# NanoV3_3.net
KiCad netlist of a schematic drawn in EAGLE
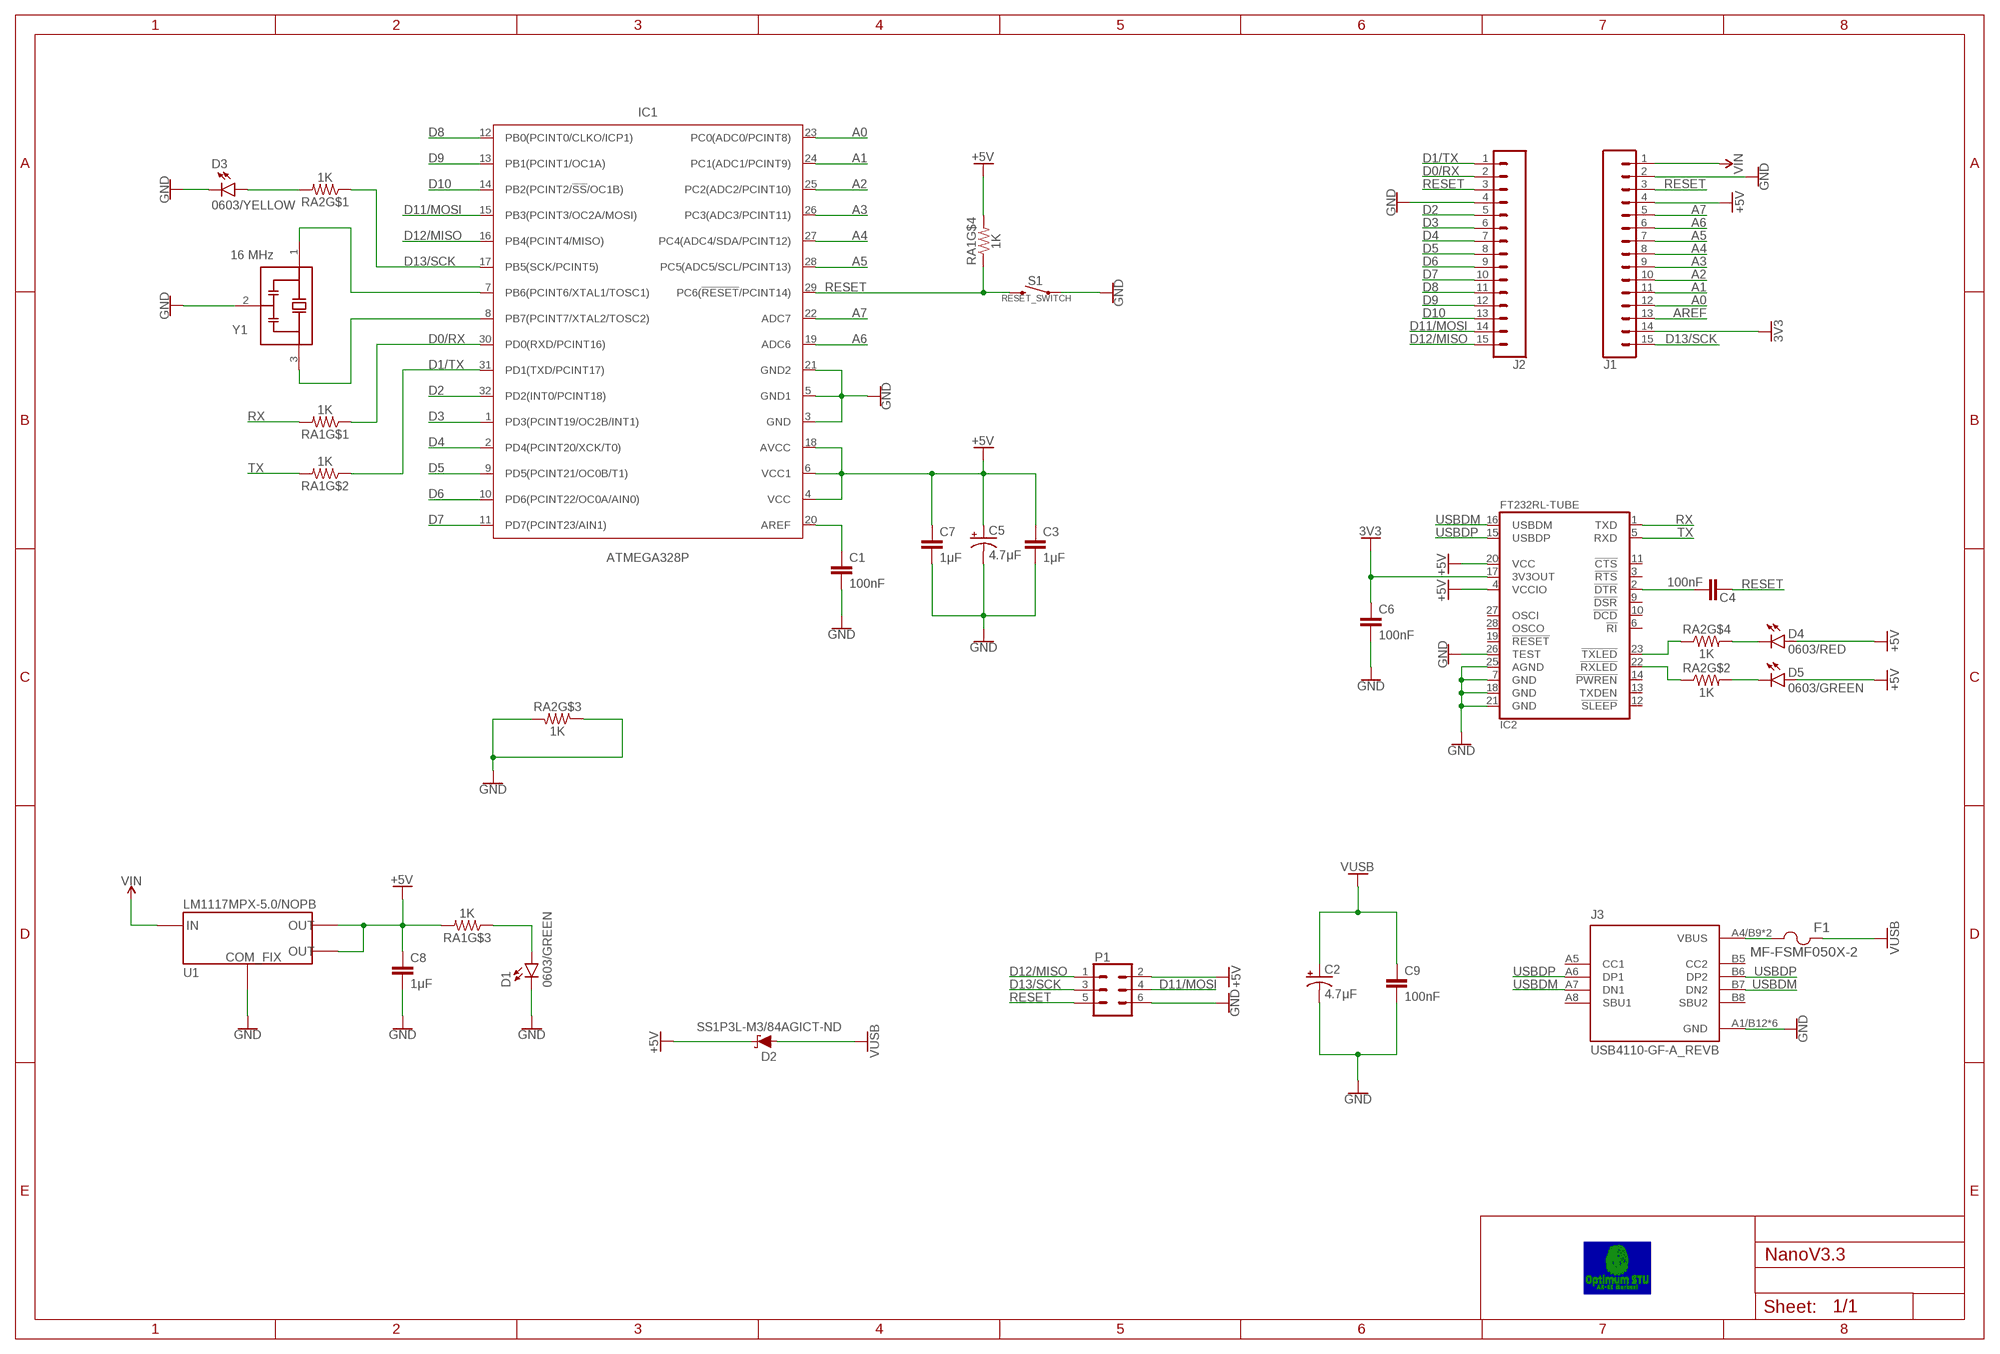
[diagram p0: schematic, sheet 1]

(export (version "E")
  (design (tool "Eeschema 10.0.6"))
  (components
    (comp (ref "C1")
      (value "100nF")
      (footprint "eagle-import:CAP_0603(1608_METRIC)")
      (libsource (lib "eagle-import") (part "100NF_0603(1608METRIC)_±10%_16V_CERAMIC_CAPACITOR_X7R"))
    )
    (comp (ref "C2")
      (value "4.7μF")
      (footprint "eagle-import:CAP_TANT_1206(3216_METRIC)_TYPE_A_MAX")
      (libsource (lib "eagle-import") (part "4.7UF_TANTALUM_CAPACITOR_MOLDED_1206(3216_METRIC)_TYPE_A_16V_4OHM"))
    )
    (comp (ref "C3")
      (value "1μF")
      (footprint "eagle-import:CAP_0603(1608_METRIC)")
      (libsource (lib "eagle-import") (part "1UF_0603(1608METRIC)_±10%_16V_CERAMIC_CAPACITOR_X7R"))
    )
    (comp (ref "C4")
      (value "100nF")
      (footprint "eagle-import:CAP_0603(1608_METRIC)")
      (libsource (lib "eagle-import") (part "100NF_0603(1608METRIC)_±10%_16V_CERAMIC_CAPACITOR_X7R"))
    )
    (comp (ref "C5")
      (value "4.7μF")
      (footprint "eagle-import:CAP_TANT_1206(3216_METRIC)_TYPE_A_MAX")
      (libsource (lib "eagle-import") (part "4.7UF_TANTALUM_CAPACITOR_MOLDED_1206(3216_METRIC)_TYPE_A_16V_4OHM"))
    )
    (comp (ref "C6")
      (value "100nF")
      (footprint "eagle-import:CAP_0603(1608_METRIC)")
      (libsource (lib "eagle-import") (part "100NF_0603(1608METRIC)_±10%_16V_CERAMIC_CAPACITOR_X7R"))
    )
    (comp (ref "C7")
      (value "1μF")
      (footprint "eagle-import:CAP_0603(1608_METRIC)")
      (libsource (lib "eagle-import") (part "1UF_0603(1608METRIC)_±10%_16V_CERAMIC_CAPACITOR_X7R"))
    )
    (comp (ref "C8")
      (value "1μF")
      (footprint "eagle-import:CAP_0603(1608_METRIC)")
      (libsource (lib "eagle-import") (part "1UF_0603(1608METRIC)_±10%_16V_CERAMIC_CAPACITOR_X7R"))
    )
    (comp (ref "C9")
      (value "100nF")
      (footprint "eagle-import:CAP_0603(1608_METRIC)")
      (libsource (lib "eagle-import") (part "100NF_0603(1608METRIC)_±10%_16V_CERAMIC_CAPACITOR_X7R"))
    )
    (comp (ref "D1")
      (value "0603/GREEN")
      (footprint "eagle-import:LED_0603(1608_METRIC)_GREEN")
      (libsource (lib "eagle-import") (part "LED_GREEN_571NM_0603(1608_METRIC)_INDICATION-DISCRETE_2V"))
    )
    (comp (ref "D2")
      (value "SS1P3L-M3/84AGICT-ND")
      (footprint "eagle-import:DO-220AA(SMP)-M")
      (fields
        (field (name "MANUFACTURER_PART_NUMBER") "SS1P3L-M3/84A")
        (field (name "COPYRIGHT") "Copyright (C) 2022 Ultra Librarian. All rights reserved.")
      )
      (libsource (lib "eagle-import") (part "SS1P3L-M3/84ADIODE_SS1P3L-M3/84A_VIS-M"))
    )
    (comp (ref "D3")
      (value "0603/YELLOW")
      (footprint "eagle-import:LED_0603(1608_METRIC)_YELLOW")
      (libsource (lib "eagle-import") (part "LED_YELLOW_591NM_0603(1608_METRIC)_INDICATION-DISCRETE_2.1V"))
    )
    (comp (ref "D4")
      (value "0603/RED")
      (footprint "eagle-import:LED_0603(1608_METRIC)_RED")
      (libsource (lib "eagle-import") (part "LED_RED_631NM_0603(1608_METRIC)_INDICATION-DISCRETE_2V"))
    )
    (comp (ref "D5")
      (value "0603/GREEN")
      (footprint "eagle-import:LED_0603(1608_METRIC)_GREEN")
      (libsource (lib "eagle-import") (part "LED_GREEN_571NM_0603(1608_METRIC)_INDICATION-DISCRETE_2V"))
    )
    (comp (ref "F1")
      (value "MF-FSMF050X-2")
      (footprint "eagle-import:PTC_FUSE_0603(1608_METRIC)")
      (fields (field (name "COPYRIGHT") "Copyright (C) 2022 Ultra Librarian. All rights reserved."))
      (libsource (lib "eagle-import") (part "MF-FSMF050X-2"))
    )
    (comp (ref "IC1")
      (value "ATMEGA328P")
      (footprint "eagle-import:32-TQFP")
      (fields (field (name "MANUFACTURER") "Microchip") (field (name "MPN") "ATmega328P-MMH"))
      (libsource (lib "eagle-import") (part "ATMEGA328P_TQFP"))
    )
    (comp (ref "IC2")
      (value "FT232RL-TUBE")
      (footprint "eagle-import:28-SSOP")
      (fields (field (name "DIGI-KEY_PART_NUMBER") "768-1306-ND") (field (name "MF") "FTDI,"))
      (libsource (lib "eagle-import") (part "FT232RL-TUBE"))
    )
    (comp (ref "J1")
      (value "CONN_15_M_180C")
      (footprint "eagle-import:HDRV15W64P254_1X15_3810X254X838B")
      (libsource (lib "eagle-import") (part "CONN_15_M_180C"))
    )
    (comp (ref "J2")
      (value "CONN_15_M_180C")
      (footprint "eagle-import:HDRV15W64P254_1X15_3810X254X838B")
      (libsource (lib "eagle-import") (part "CONN_15_M_180C"))
    )
    (comp (ref "J3")
      (value "USB4110-GF-A_REVB")
      (footprint "eagle-import:GCT_USB4110-GF-A_REVB")
      (fields (field (name "MF") "GCT") (field (name "MP") "USB4110-GF-A"))
      (libsource (lib "eagle-import") (part "USB4110-GF-A_REVB"))
    )
    (comp (ref "P1")
      (value "CONN_2X3_M_180C")
      (footprint "eagle-import:HDRV6W64P254_2X3_762X508X838B")
      (libsource (lib "eagle-import") (part "CONN_2X3_M_180C"))
    )
    (comp (ref "RA1")
      (value "1K")
      (footprint "eagle-import:RESISTOR_ARRAY_1206(3216_METRIC)_WIDE")
      (libsource (lib "eagle-import") (part "1KOHM_ARRAY_4_ELEMENT_ISOLATED_NETWORK/ARRAY_±5%_62.5MW_FOR_PER_RESISTOR_±200PPM/°C_1206(3216_METRIC),CONVEX,LONG_SIDE_TERMINALS"))
    )
    (comp (ref "RA2")
      (value "1K")
      (footprint "eagle-import:RESISTOR_ARRAY_1206(3216_METRIC)_WIDE")
      (libsource (lib "eagle-import") (part "1KOHM_ARRAY_4_ELEMENT_ISOLATED_NETWORK/ARRAY_±5%_62.5MW_FOR_PER_RESISTOR_±200PPM/°C_1206(3216_METRIC),CONVEX,LONG_SIDE_TERMINALS"))
    )
    (comp (ref "S1")
      (value "RESET SWITCH")
      (footprint "eagle-import:SW_TS09-63-25-WT-260-SMT-TR")
      (libsource (lib "eagle-import") (part "RS-282C05A3-SM_RT"))
    )
    (comp (ref "U1")
      (value "LM1117MPX-5.0/NOPB")
      (footprint "eagle-import:SOT-223-4")
      (libsource (lib "eagle-import") (part "LM1117MPX-5.0/NOPB_LINEAR_VOLTAGE_REGULATOR_IC_POSITIVE_FIXED_1OUTPUT_800MA_SOT-223-4"))
    )
    (comp (ref "Y1")
      (value "16 MHz")
      (footprint "eagle-import:RESONATOR_SMD-3(3.20MMX1.30MM)")
      (fields
        (field (name "DIGI-KEY_PART_NUMBER") "490-CSTNE16M0V53L000R0TR-ND")
        (field (name "MF") "Murata Electronics")
        (field (name "MP") "CSTNE16M0V53L000R0")
      )
      (libsource (lib "eagle-import") (part "CSTNE16M0V53L000R0_16MHZ_CERAMIC_RESONATOR_BUILT-IN_CAPACITOR_15PF_±0.2%_40OHMS-40°C~85°C_SURFACE_MOUNT"))
    )
  )
  (nets
    (net (code "1") (name "+5V") (class "Default")
      (node (ref "C3") (pin "1") (pinfunction "1_1") (pintype "passive"))
      (node (ref "C5") (pin "1") (pinfunction "+_1") (pintype "passive"))
      (node (ref "C7") (pin "1") (pinfunction "1_1") (pintype "passive"))
      (node (ref "C8") (pin "1") (pinfunction "1_1") (pintype "passive"))
      (node (ref "D2") (pin "1") (pinfunction "C_1") (pintype "passive"))
      (node (ref "D4") (pin "A") (pinfunction "A_A") (pintype "passive"))
      (node (ref "D5") (pin "A") (pinfunction "A_A") (pintype "passive"))
      (node (ref "IC1") (pin "18") (pinfunction "AVCC_18") (pintype "power_in"))
      (node (ref "IC1") (pin "4") (pinfunction "VCC_4") (pintype "power_in"))
      (node (ref "IC1") (pin "6") (pinfunction "VCC1_6") (pintype "power_in"))
      (node (ref "IC2") (pin "20") (pinfunction "VCC_20") (pintype "power_in"))
      (node (ref "IC2") (pin "4") (pinfunction "VCCIO_4") (pintype "power_in"))
      (node (ref "J1") (pin "4") (pinfunction "4_4") (pintype "passive"))
      (node (ref "P1") (pin "2") (pinfunction "2_2") (pintype "bidirectional"))
      (node (ref "RA1") (pin "5") (pinfunction "2_5") (pintype "passive"))
      (node (ref "RA1") (pin "6") (pinfunction "2_6") (pintype "passive"))
      (node (ref "U1") (pin "2") (pinfunction "OUTPUT_JUNCTİON_2") (pintype "output"))
      (node (ref "U1") (pin "4") (pinfunction "OUTPUT_TAB_4") (pintype "output"))
    )
    (net (code "2") (name "/A0") (class "Default")
      (node (ref "IC1") (pin "23") (pinfunction "PC0(ADC0/PCINT8)_23") (pintype "bidirectional"))
      (node (ref "J1") (pin "12") (pinfunction "12_12") (pintype "passive"))
    )
    (net (code "3") (name "/A1") (class "Default")
      (node (ref "IC1") (pin "24") (pinfunction "PC1(ADC1/PCINT9)_24") (pintype "bidirectional"))
      (node (ref "J1") (pin "11") (pinfunction "11_11") (pintype "passive"))
    )
    (net (code "4") (name "/A2") (class "Default")
      (node (ref "IC1") (pin "25") (pinfunction "PC2(ADC2/PCINT10)_25") (pintype "bidirectional"))
      (node (ref "J1") (pin "10") (pinfunction "10_10") (pintype "passive"))
    )
    (net (code "5") (name "/A3") (class "Default")
      (node (ref "IC1") (pin "26") (pinfunction "PC3(ADC3/PCINT11)_26") (pintype "bidirectional"))
      (node (ref "J1") (pin "9") (pinfunction "9_9") (pintype "passive"))
    )
    (net (code "6") (name "/A4") (class "Default")
      (node (ref "IC1") (pin "27") (pinfunction "PC4(ADC4/SDA/PCINT12)_27") (pintype "bidirectional"))
      (node (ref "J1") (pin "8") (pinfunction "8_8") (pintype "passive"))
    )
    (net (code "7") (name "/A5") (class "Default")
      (node (ref "IC1") (pin "28") (pinfunction "PC5(ADC5/SCL/PCINT13)_28") (pintype "bidirectional"))
      (node (ref "J1") (pin "7") (pinfunction "7_7") (pintype "passive"))
    )
    (net (code "8") (name "/A6") (class "Default")
      (node (ref "IC1") (pin "19") (pinfunction "ADC6_19") (pintype "bidirectional"))
      (node (ref "J1") (pin "6") (pinfunction "6_6") (pintype "passive"))
    )
    (net (code "9") (name "/A7") (class "Default")
      (node (ref "IC1") (pin "22") (pinfunction "ADC7_22") (pintype "bidirectional"))
      (node (ref "J1") (pin "5") (pinfunction "5_5") (pintype "passive"))
    )
    (net (code "10") (name "/AREF") (class "Default")
      (node (ref "C1") (pin "1") (pinfunction "1_1") (pintype "passive"))
      (node (ref "IC1") (pin "20") (pinfunction "AREF_20") (pintype "power_in"))
      (node (ref "J1") (pin "13") (pinfunction "13_13") (pintype "passive"))
    )
    (net (code "11") (name "/D0{slash}RX") (class "Default")
      (node (ref "IC1") (pin "30") (pinfunction "PD0(RXD/PCINT16)_30") (pintype "bidirectional"))
      (node (ref "J2") (pin "2") (pinfunction "2_2") (pintype "passive"))
      (node (ref "RA1") (pin "1") (pinfunction "1_1") (pintype "passive"))
    )
    (net (code "12") (name "/D1{slash}TX") (class "Default")
      (node (ref "IC1") (pin "31") (pinfunction "PD1(TXD/PCINT17)_31") (pintype "bidirectional"))
      (node (ref "J2") (pin "1") (pinfunction "1_1") (pintype "passive"))
      (node (ref "RA1") (pin "2") (pinfunction "1_2") (pintype "passive"))
    )
    (net (code "13") (name "/D2") (class "Default")
      (node (ref "IC1") (pin "32") (pinfunction "PD2(INT0/PCINT18)_32") (pintype "bidirectional"))
      (node (ref "J2") (pin "5") (pinfunction "5_5") (pintype "passive"))
    )
    (net (code "14") (name "/D3") (class "Default")
      (node (ref "IC1") (pin "1") (pinfunction "PD3(PCINT19/OC2B/INT1)_1") (pintype "bidirectional"))
      (node (ref "J2") (pin "6") (pinfunction "6_6") (pintype "passive"))
    )
    (net (code "15") (name "/D4") (class "Default")
      (node (ref "IC1") (pin "2") (pinfunction "PD4(PCINT20/XCK/T0)_2") (pintype "bidirectional"))
      (node (ref "J2") (pin "7") (pinfunction "7_7") (pintype "passive"))
    )
    (net (code "16") (name "/D5") (class "Default")
      (node (ref "IC1") (pin "9") (pinfunction "PD5(PCINT21/OC0B/T1)_9") (pintype "bidirectional"))
      (node (ref "J2") (pin "8") (pinfunction "8_8") (pintype "passive"))
    )
    (net (code "17") (name "/D6") (class "Default")
      (node (ref "IC1") (pin "10") (pinfunction "PD6(PCINT22/OC0A/AIN0)_10") (pintype "bidirectional"))
      (node (ref "J2") (pin "9") (pinfunction "9_9") (pintype "passive"))
    )
    (net (code "18") (name "/D7") (class "Default")
      (node (ref "IC1") (pin "11") (pinfunction "PD7(PCINT23/AIN1)_11") (pintype "bidirectional"))
      (node (ref "J2") (pin "10") (pinfunction "10_10") (pintype "passive"))
    )
    (net (code "19") (name "/D8") (class "Default")
      (node (ref "IC1") (pin "12") (pinfunction "PB0(PCINT0/CLKO/ICP1)_12") (pintype "bidirectional"))
      (node (ref "J2") (pin "11") (pinfunction "11_11") (pintype "passive"))
    )
    (net (code "20") (name "/D9") (class "Default")
      (node (ref "IC1") (pin "13") (pinfunction "PB1(PCINT1/OC1A)_13") (pintype "bidirectional"))
      (node (ref "J2") (pin "12") (pinfunction "12_12") (pintype "passive"))
    )
    (net (code "21") (name "/D10") (class "Default")
      (node (ref "IC1") (pin "14") (pinfunction "PB2(PCINT2/~{SS}/OC1B)_14") (pintype "bidirectional"))
      (node (ref "J2") (pin "13") (pinfunction "13_13") (pintype "passive"))
    )
    (net (code "22") (name "/D11{slash}MOSI") (class "Default")
      (node (ref "IC1") (pin "15") (pinfunction "PB3(PCINT3/OC2A/MOSI)_15") (pintype "bidirectional"))
      (node (ref "J2") (pin "14") (pinfunction "14_14") (pintype "passive"))
      (node (ref "P1") (pin "4") (pinfunction "4_4") (pintype "bidirectional"))
    )
    (net (code "23") (name "/D12{slash}MISO") (class "Default")
      (node (ref "IC1") (pin "16") (pinfunction "PB4(PCINT4/MISO)_16") (pintype "bidirectional"))
      (node (ref "J2") (pin "15") (pinfunction "15_15") (pintype "passive"))
      (node (ref "P1") (pin "1") (pinfunction "1_1") (pintype "bidirectional"))
    )
    (net (code "24") (name "/D13{slash}SCK") (class "Default")
      (node (ref "IC1") (pin "17") (pinfunction "PB5(SCK/PCINT5)_17") (pintype "bidirectional"))
      (node (ref "J1") (pin "15") (pinfunction "15_15") (pintype "passive"))
      (node (ref "P1") (pin "3") (pinfunction "3_3") (pintype "bidirectional"))
      (node (ref "RA2") (pin "1") (pinfunction "1_1") (pintype "passive"))
    )
    (net (code "25") (name "/RESET") (class "Default")
      (node (ref "C4") (pin "1") (pinfunction "1_1") (pintype "passive"))
      (node (ref "IC1") (pin "29") (pinfunction "PC6(~{RESET}/PCINT14)_29") (pintype "bidirectional"))
      (node (ref "J1") (pin "3") (pinfunction "3_3") (pintype "passive"))
      (node (ref "J2") (pin "3") (pinfunction "3_3") (pintype "passive"))
      (node (ref "P1") (pin "5") (pinfunction "5_5") (pintype "bidirectional"))
      (node (ref "RA1") (pin "4") (pinfunction "1_4") (pintype "passive"))
      (node (ref "S1") (pin "2") (pinfunction "2_2") (pintype "passive"))
    )
    (net (code "26") (name "/RX") (class "Default")
      (node (ref "IC2") (pin "1") (pinfunction "TXD_1") (pintype "output"))
      (node (ref "RA1") (pin "8") (pinfunction "2_8") (pintype "passive"))
    )
    (net (code "27") (name "/TX") (class "Default")
      (node (ref "IC2") (pin "5") (pinfunction "RXD_5") (pintype "input"))
      (node (ref "RA1") (pin "7") (pinfunction "2_7") (pintype "passive"))
    )
    (net (code "28") (name "/USBDM") (class "Default")
      (node (ref "IC2") (pin "16") (pinfunction "USBDM_16") (pintype "bidirectional"))
      (node (ref "J3") (pin "A7") (pinfunction "DN1_A7") (pintype "bidirectional"))
      (node (ref "J3") (pin "B7") (pinfunction "DN2_B7") (pintype "bidirectional"))
    )
    (net (code "29") (name "/USBDP") (class "Default")
      (node (ref "IC2") (pin "15") (pinfunction "USBDP_15") (pintype "bidirectional"))
      (node (ref "J3") (pin "A6") (pinfunction "DP1_A6") (pintype "bidirectional"))
      (node (ref "J3") (pin "B6") (pinfunction "DP2_B6") (pintype "bidirectional"))
    )
    (net (code "30") (name "3V3") (class "Default")
      (node (ref "C6") (pin "1") (pinfunction "1_1") (pintype "passive"))
      (node (ref "IC2") (pin "17") (pinfunction "3V3OUT_17") (pintype "power_in"))
      (node (ref "J1") (pin "14") (pinfunction "14_14") (pintype "passive"))
    )
    (net (code "31") (name "GND") (class "Default")
      (node (ref "C1") (pin "2") (pinfunction "2_2") (pintype "passive"))
      (node (ref "C2") (pin "2") (pinfunction "-_2") (pintype "passive"))
      (node (ref "C3") (pin "2") (pinfunction "2_2") (pintype "passive"))
      (node (ref "C5") (pin "2") (pinfunction "-_2") (pintype "passive"))
      (node (ref "C6") (pin "2") (pinfunction "2_2") (pintype "passive"))
      (node (ref "C7") (pin "2") (pinfunction "2_2") (pintype "passive"))
      (node (ref "C8") (pin "2") (pinfunction "2_2") (pintype "passive"))
      (node (ref "C9") (pin "2") (pinfunction "2_2") (pintype "passive"))
      (node (ref "D1") (pin "C") (pinfunction "C_C") (pintype "passive"))
      (node (ref "D3") (pin "C") (pinfunction "C_C") (pintype "passive"))
      (node (ref "IC1") (pin "21") (pinfunction "GND2_21") (pintype "passive"))
      (node (ref "IC1") (pin "3") (pinfunction "GND_3") (pintype "passive"))
      (node (ref "IC1") (pin "5") (pinfunction "GND1_5") (pintype "passive"))
      (node (ref "IC2") (pin "18") (pinfunction "GND_18") (pintype "power_in"))
      (node (ref "IC2") (pin "21") (pinfunction "GND_21") (pintype "power_in"))
      (node (ref "IC2") (pin "25") (pinfunction "AGND_25") (pintype "power_in"))
      (node (ref "IC2") (pin "26") (pinfunction "TEST_26") (pintype "input"))
      (node (ref "IC2") (pin "7") (pinfunction "GND_7") (pintype "power_in"))
      (node (ref "J1") (pin "2") (pinfunction "2_2") (pintype "passive"))
      (node (ref "J2") (pin "4") (pinfunction "4_4") (pintype "passive"))
      (node (ref "J3") (pin "A1/B12") (pinfunction "GND_A1/B12") (pintype "power_in"))
      (node (ref "J3") (pin "B1/A12") (pinfunction "GND_B1/A12") (pintype "power_in"))
      (node (ref "J3") (pin "S1") (pinfunction "GND_S1") (pintype "power_in"))
      (node (ref "J3") (pin "S2") (pinfunction "GND_S2") (pintype "power_in"))
      (node (ref "J3") (pin "S3") (pinfunction "GND_S3") (pintype "power_in"))
      (node (ref "J3") (pin "S4") (pinfunction "GND_S4") (pintype "power_in"))
      (node (ref "P1") (pin "6") (pinfunction "6_6") (pintype "bidirectional"))
      (node (ref "RA2") (pin "3") (pinfunction "1_3") (pintype "passive"))
      (node (ref "RA2") (pin "6") (pinfunction "2_6") (pintype "passive"))
      (node (ref "S1") (pin "1") (pinfunction "1_1") (pintype "passive"))
      (node (ref "U1") (pin "1") (pinfunction "COMMON_FIXED_1") (pintype "input"))
      (node (ref "Y1") (pin "2") (pinfunction "GND_2") (pintype "power_in"))
    )
    (net (code "32") (name "Net-(F1-Pad1)") (class "Default")
      (node (ref "F1") (pin "1") (pinfunction "1_1") (pintype "passive"))
      (node (ref "J3") (pin "A4/B9") (pinfunction "VBUS_A4/B9") (pintype "power_in"))
      (node (ref "J3") (pin "B4/A9") (pinfunction "VBUS_B4/A9") (pintype "power_in"))
    )
    (net (code "33") (name "Net-(IC1-PB6(PCINT6{slash}XTAL1{slash}TOSC1))") (class "Default")
      (node (ref "IC1") (pin "7") (pinfunction "PB6(PCINT6/XTAL1/TOSC1)_7") (pintype "input"))
      (node (ref "Y1") (pin "1") (pinfunction "IN_1") (pintype "input"))
    )
    (net (code "34") (name "Net-(IC1-PB7(PCINT7{slash}XTAL2{slash}TOSC2))") (class "Default")
      (node (ref "IC1") (pin "8") (pinfunction "PB7(PCINT7/XTAL2/TOSC2)_8") (pintype "input"))
      (node (ref "Y1") (pin "3") (pinfunction "OUT_3") (pintype "output"))
    )
    (net (code "35") (name "Net-(IC2-~{DTR})") (class "Default")
      (node (ref "C4") (pin "2") (pinfunction "2_2") (pintype "passive"))
      (node (ref "IC2") (pin "2") (pinfunction "~{DTR}_2") (pintype "output"))
    )
    (net (code "36") (name "Net-(IC2-~{RXLED})") (class "Default")
      (node (ref "IC2") (pin "22") (pinfunction "~{RXLED}_22") (pintype "input"))
      (node (ref "RA2") (pin "2") (pinfunction "1_2") (pintype "passive"))
    )
    (net (code "37") (name "Net-(IC2-~{TXLED})") (class "Default")
      (node (ref "IC2") (pin "23") (pinfunction "~{TXLED}_23") (pintype "input"))
      (node (ref "RA2") (pin "4") (pinfunction "1_4") (pintype "passive"))
    )
    (net (code "38") (name "Net-(RA1C-1)") (class "Default")
      (node (ref "D1") (pin "A") (pinfunction "A_A") (pintype "passive"))
      (node (ref "RA1") (pin "3") (pinfunction "1_3") (pintype "passive"))
    )
    (net (code "39") (name "Net-(RA2A-2)") (class "Default")
      (node (ref "D3") (pin "A") (pinfunction "A_A") (pintype "passive"))
      (node (ref "RA2") (pin "8") (pinfunction "2_8") (pintype "passive"))
    )
    (net (code "40") (name "Net-(RA2B-2)") (class "Default")
      (node (ref "D5") (pin "C") (pinfunction "C_C") (pintype "passive"))
      (node (ref "RA2") (pin "7") (pinfunction "2_7") (pintype "passive"))
    )
    (net (code "41") (name "Net-(RA2D-2)") (class "Default")
      (node (ref "D4") (pin "C") (pinfunction "C_C") (pintype "passive"))
      (node (ref "RA2") (pin "5") (pinfunction "2_5") (pintype "passive"))
    )
    (net (code "42") (name "VIN") (class "Default")
      (node (ref "J1") (pin "1") (pinfunction "1_1") (pintype "passive"))
      (node (ref "U1") (pin "3") (pinfunction "INPUT_3") (pintype "input"))
    )
    (net (code "43") (name "VUSB") (class "Default")
      (node (ref "C2") (pin "1") (pinfunction "+_1") (pintype "passive"))
      (node (ref "C9") (pin "1") (pinfunction "1_1") (pintype "passive"))
      (node (ref "D2") (pin "2") (pinfunction "A_2") (pintype "passive"))
      (node (ref "F1") (pin "2") (pinfunction "2_2") (pintype "passive"))
    )
    (net (code "44") (name "unconnected-(IC2-OSCI-Pad27)") (class "Default")
      (node (ref "IC2") (pin "27") (pinfunction "OSCI_27") (pintype "no_connect"))
    )
    (net (code "45") (name "unconnected-(IC2-OSCO-Pad28)") (class "Default")
      (node (ref "IC2") (pin "28") (pinfunction "OSCO_28") (pintype "output"))
    )
    (net (code "46") (name "unconnected-(IC2-TXDEN-Pad13)") (class "Default")
      (node (ref "IC2") (pin "13") (pinfunction "TXDEN_13") (pintype "no_connect"))
    )
    (net (code "47") (name "unconnected-(IC2-~{CTS}-Pad11)") (class "Default")
      (node (ref "IC2") (pin "11") (pinfunction "~{CTS}_11") (pintype "input"))
    )
    (net (code "48") (name "unconnected-(IC2-~{DCD}-Pad10)") (class "Default")
      (node (ref "IC2") (pin "10") (pinfunction "~{DCD}_10") (pintype "no_connect"))
    )
    (net (code "49") (name "unconnected-(IC2-~{DSR}-Pad9)") (class "Default")
      (node (ref "IC2") (pin "9") (pinfunction "~{DSR}_9") (pintype "no_connect"))
    )
    (net (code "50") (name "unconnected-(IC2-~{PWREN}-Pad14)") (class "Default")
      (node (ref "IC2") (pin "14") (pinfunction "~{PWREN}_14") (pintype "no_connect"))
    )
    (net (code "51") (name "unconnected-(IC2-~{RESET}-Pad19)") (class "Default")
      (node (ref "IC2") (pin "19") (pinfunction "~{RESET}_19") (pintype "no_connect"))
    )
    (net (code "52") (name "unconnected-(IC2-~{RI}-Pad6)") (class "Default")
      (node (ref "IC2") (pin "6") (pinfunction "~{RI}_6") (pintype "no_connect"))
    )
    (net (code "53") (name "unconnected-(IC2-~{RTS}-Pad3)") (class "Default")
      (node (ref "IC2") (pin "3") (pinfunction "~{RTS}_3") (pintype "output"))
    )
    (net (code "54") (name "unconnected-(IC2-~{SLEEP}-Pad12)") (class "Default")
      (node (ref "IC2") (pin "12") (pinfunction "~{SLEEP}_12") (pintype "no_connect"))
    )
    (net (code "55") (name "unconnected-(J3-CC1-PadA5)") (class "Default")
      (node (ref "J3") (pin "A5") (pinfunction "CC1_A5") (pintype "bidirectional"))
    )
    (net (code "56") (name "unconnected-(J3-CC2-PadB5)") (class "Default")
      (node (ref "J3") (pin "B5") (pinfunction "CC2_B5") (pintype "bidirectional"))
    )
    (net (code "57") (name "unconnected-(J3-SBU1-PadA8)") (class "Default")
      (node (ref "J3") (pin "A8") (pinfunction "SBU1_A8") (pintype "bidirectional"))
    )
    (net (code "58") (name "unconnected-(J3-SBU2-PadB8)") (class "Default")
      (node (ref "J3") (pin "B8") (pinfunction "SBU2_B8") (pintype "bidirectional"))
    )
  )
)
